# Connector.net
KiCad netlist of a schematic drawn in Altium Designer
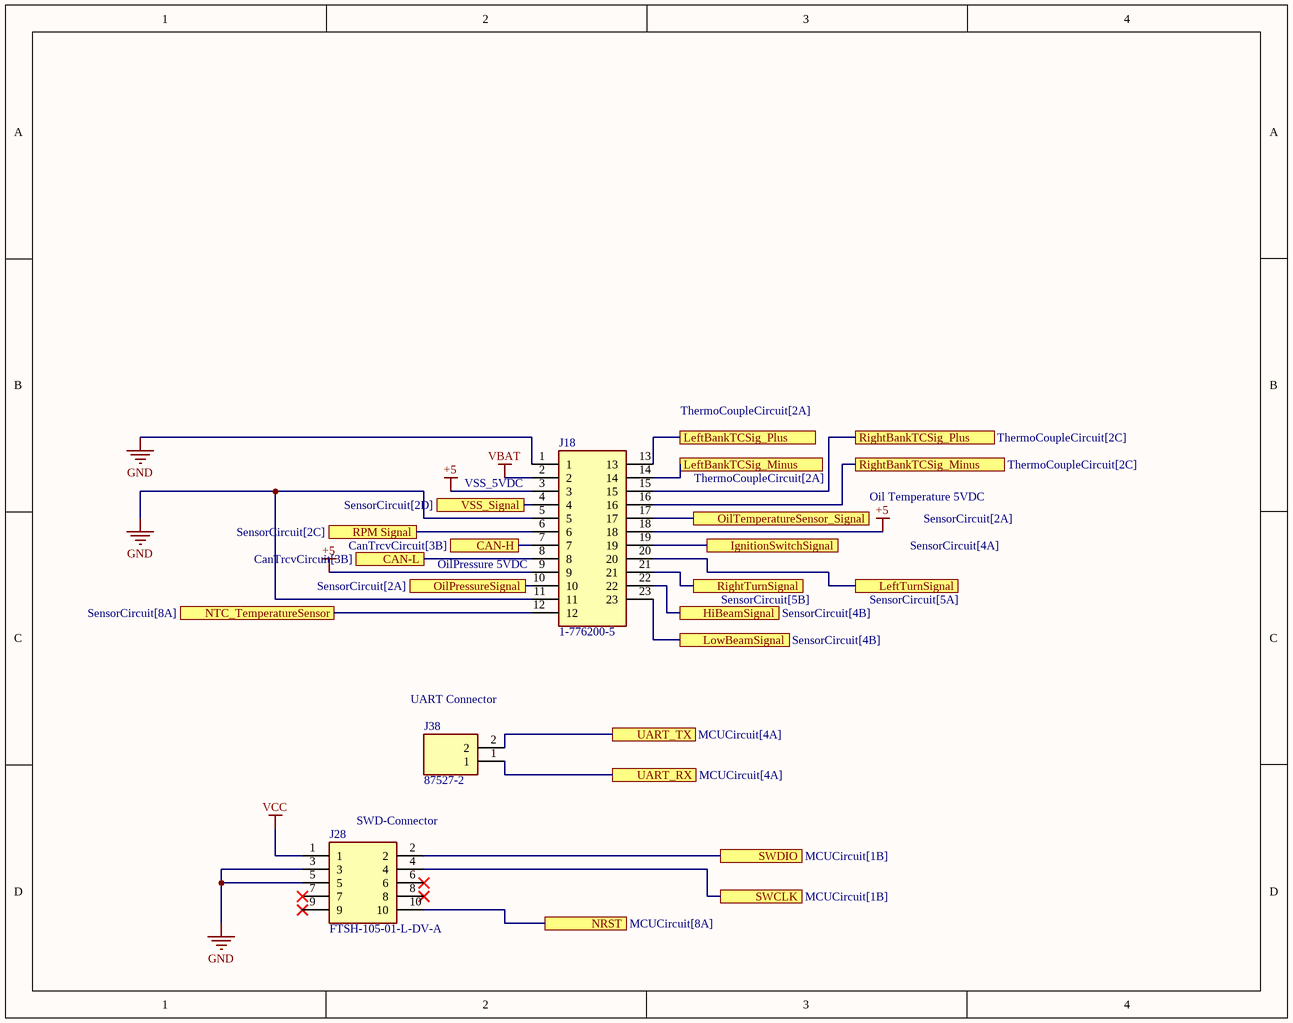
[diagram p0: Connector.SchDoc]

(export (version "E")
  (design (tool "Eeschema 10.0.6"))
  (components
    (comp (ref "J18")
      (value "1-776200-5")
      (footprint "17762005")
      (description "Connector")
      (fields (field (name "MOUSER PART NUMBER") "571-1-776200-5"))
      (libsource (lib "Connector") (part "1-776200-5"))
    )
    (comp (ref "J28")
      (value "FTSH-105-01-L-DV-A")
      (footprint "SamacSys:FTSH-105-XX-YYY-DV-A")
      (description "Connector")
      (fields (field (name "MOUSER PART NUMBER") "200-FTSH10501LDVA"))
      (libsource (lib "SamacSys") (part "FTSH-105-01-L-DV-A"))
    )
    (comp (ref "J38")
      (value "87527-2")
      (footprint "SamacSys:HDRV2W66P0X254_1X2_467X244X1044P")
      (description "Connector")
      (fields (field (name "MOUSER PART NUMBER") "571-875272"))
      (libsource (lib "SamacSys") (part "87527-2"))
    )
  )
  (nets
    (net (code "1") (name "+5") (class "Default")
      (node (ref "J18") (pin "18") (pinfunction "18_18") (pintype "passive"))
      (node (ref "J18") (pin "3") (pinfunction "3_3") (pintype "passive"))
      (node (ref "J18") (pin "9") (pinfunction "9_9") (pintype "passive"))
    )
    (net (code "2") (name "/CAN-H") (class "Default")
      (node (ref "J18") (pin "7") (pinfunction "7_7") (pintype "passive"))
    )
    (net (code "3") (name "/CAN-L") (class "Default")
      (node (ref "J18") (pin "8") (pinfunction "8_8") (pintype "passive"))
    )
    (net (code "4") (name "/HiBeamSignal") (class "Default")
      (node (ref "J18") (pin "22") (pinfunction "22_22") (pintype "passive"))
    )
    (net (code "5") (name "/IgnitionSwitchSignal") (class "Default")
      (node (ref "J18") (pin "19") (pinfunction "19_19") (pintype "passive"))
    )
    (net (code "6") (name "/LeftBankTCSig_Minus") (class "Default")
      (node (ref "J18") (pin "14") (pinfunction "14_14") (pintype "passive"))
    )
    (net (code "7") (name "/LeftBankTCSig_Plus") (class "Default")
      (node (ref "J18") (pin "13") (pinfunction "13_13") (pintype "passive"))
    )
    (net (code "8") (name "/LeftTurnSignal") (class "Default")
      (node (ref "J18") (pin "20") (pinfunction "20_20") (pintype "passive"))
    )
    (net (code "9") (name "/LowBeamSignal") (class "Default")
      (node (ref "J18") (pin "23") (pinfunction "23_23") (pintype "passive"))
    )
    (net (code "10") (name "/NRST") (class "Default")
      (node (ref "J28") (pin "10") (pinfunction "10_10") (pintype "passive"))
    )
    (net (code "11") (name "/NTC_TemperatureSensor") (class "Default")
      (node (ref "J18") (pin "12") (pinfunction "12_12") (pintype "passive"))
    )
    (net (code "12") (name "/OilPressureSignal") (class "Default")
      (node (ref "J18") (pin "10") (pinfunction "10_10") (pintype "passive"))
    )
    (net (code "13") (name "/OilTemperatureSensor_Signal") (class "Default")
      (node (ref "J18") (pin "17") (pinfunction "17_17") (pintype "passive"))
    )
    (net (code "14") (name "/RPM Signal") (class "Default")
      (node (ref "J18") (pin "6") (pinfunction "6_6") (pintype "passive"))
    )
    (net (code "15") (name "/RightBankTCSig_Minus") (class "Default")
      (node (ref "J18") (pin "16") (pinfunction "16_16") (pintype "passive"))
    )
    (net (code "16") (name "/RightBankTCSig_Plus") (class "Default")
      (node (ref "J18") (pin "15") (pinfunction "15_15") (pintype "passive"))
    )
    (net (code "17") (name "/RightTurnSignal") (class "Default")
      (node (ref "J18") (pin "21") (pinfunction "21_21") (pintype "passive"))
    )
    (net (code "18") (name "/SWCLK") (class "Default")
      (node (ref "J28") (pin "4") (pinfunction "4_4") (pintype "passive"))
    )
    (net (code "19") (name "/SWDIO") (class "Default")
      (node (ref "J28") (pin "2") (pinfunction "2_2") (pintype "passive"))
    )
    (net (code "20") (name "/UART_RX") (class "Default")
      (node (ref "J38") (pin "1") (pinfunction "1_1") (pintype "passive"))
    )
    (net (code "21") (name "/UART_TX") (class "Default")
      (node (ref "J38") (pin "2") (pinfunction "2_2") (pintype "passive"))
    )
    (net (code "22") (name "/VSS_Signal") (class "Default")
      (node (ref "J18") (pin "4") (pinfunction "4_4") (pintype "passive"))
    )
    (net (code "23") (name "GND") (class "Default")
      (node (ref "J18") (pin "1") (pinfunction "1_1") (pintype "passive"))
      (node (ref "J18") (pin "11") (pinfunction "11_11") (pintype "passive"))
      (node (ref "J18") (pin "5") (pinfunction "5_5") (pintype "passive"))
      (node (ref "J28") (pin "3") (pinfunction "3_3") (pintype "passive"))
      (node (ref "J28") (pin "5") (pinfunction "5_5") (pintype "passive"))
    )
    (net (code "24") (name "VBAT") (class "Default")
      (node (ref "J18") (pin "2") (pinfunction "2_2") (pintype "passive"))
    )
    (net (code "25") (name "VCC") (class "Default")
      (node (ref "J28") (pin "1") (pinfunction "1_1") (pintype "passive"))
    )
    (net (code "26") (name "unconnected-(J28-Pad6)") (class "Default")
      (node (ref "J28") (pin "6") (pinfunction "6_6") (pintype "passive+no_connect"))
    )
    (net (code "27") (name "unconnected-(J28-Pad7)") (class "Default")
      (node (ref "J28") (pin "7") (pinfunction "7_7") (pintype "passive+no_connect"))
    )
    (net (code "28") (name "unconnected-(J28-Pad8)") (class "Default")
      (node (ref "J28") (pin "8") (pinfunction "8_8") (pintype "passive+no_connect"))
    )
    (net (code "29") (name "unconnected-(J28-Pad9)") (class "Default")
      (node (ref "J28") (pin "9") (pinfunction "9_9") (pintype "passive+no_connect"))
    )
  )
)
